# IO.net
KiCad netlist of a schematic drawn in Altium Designer
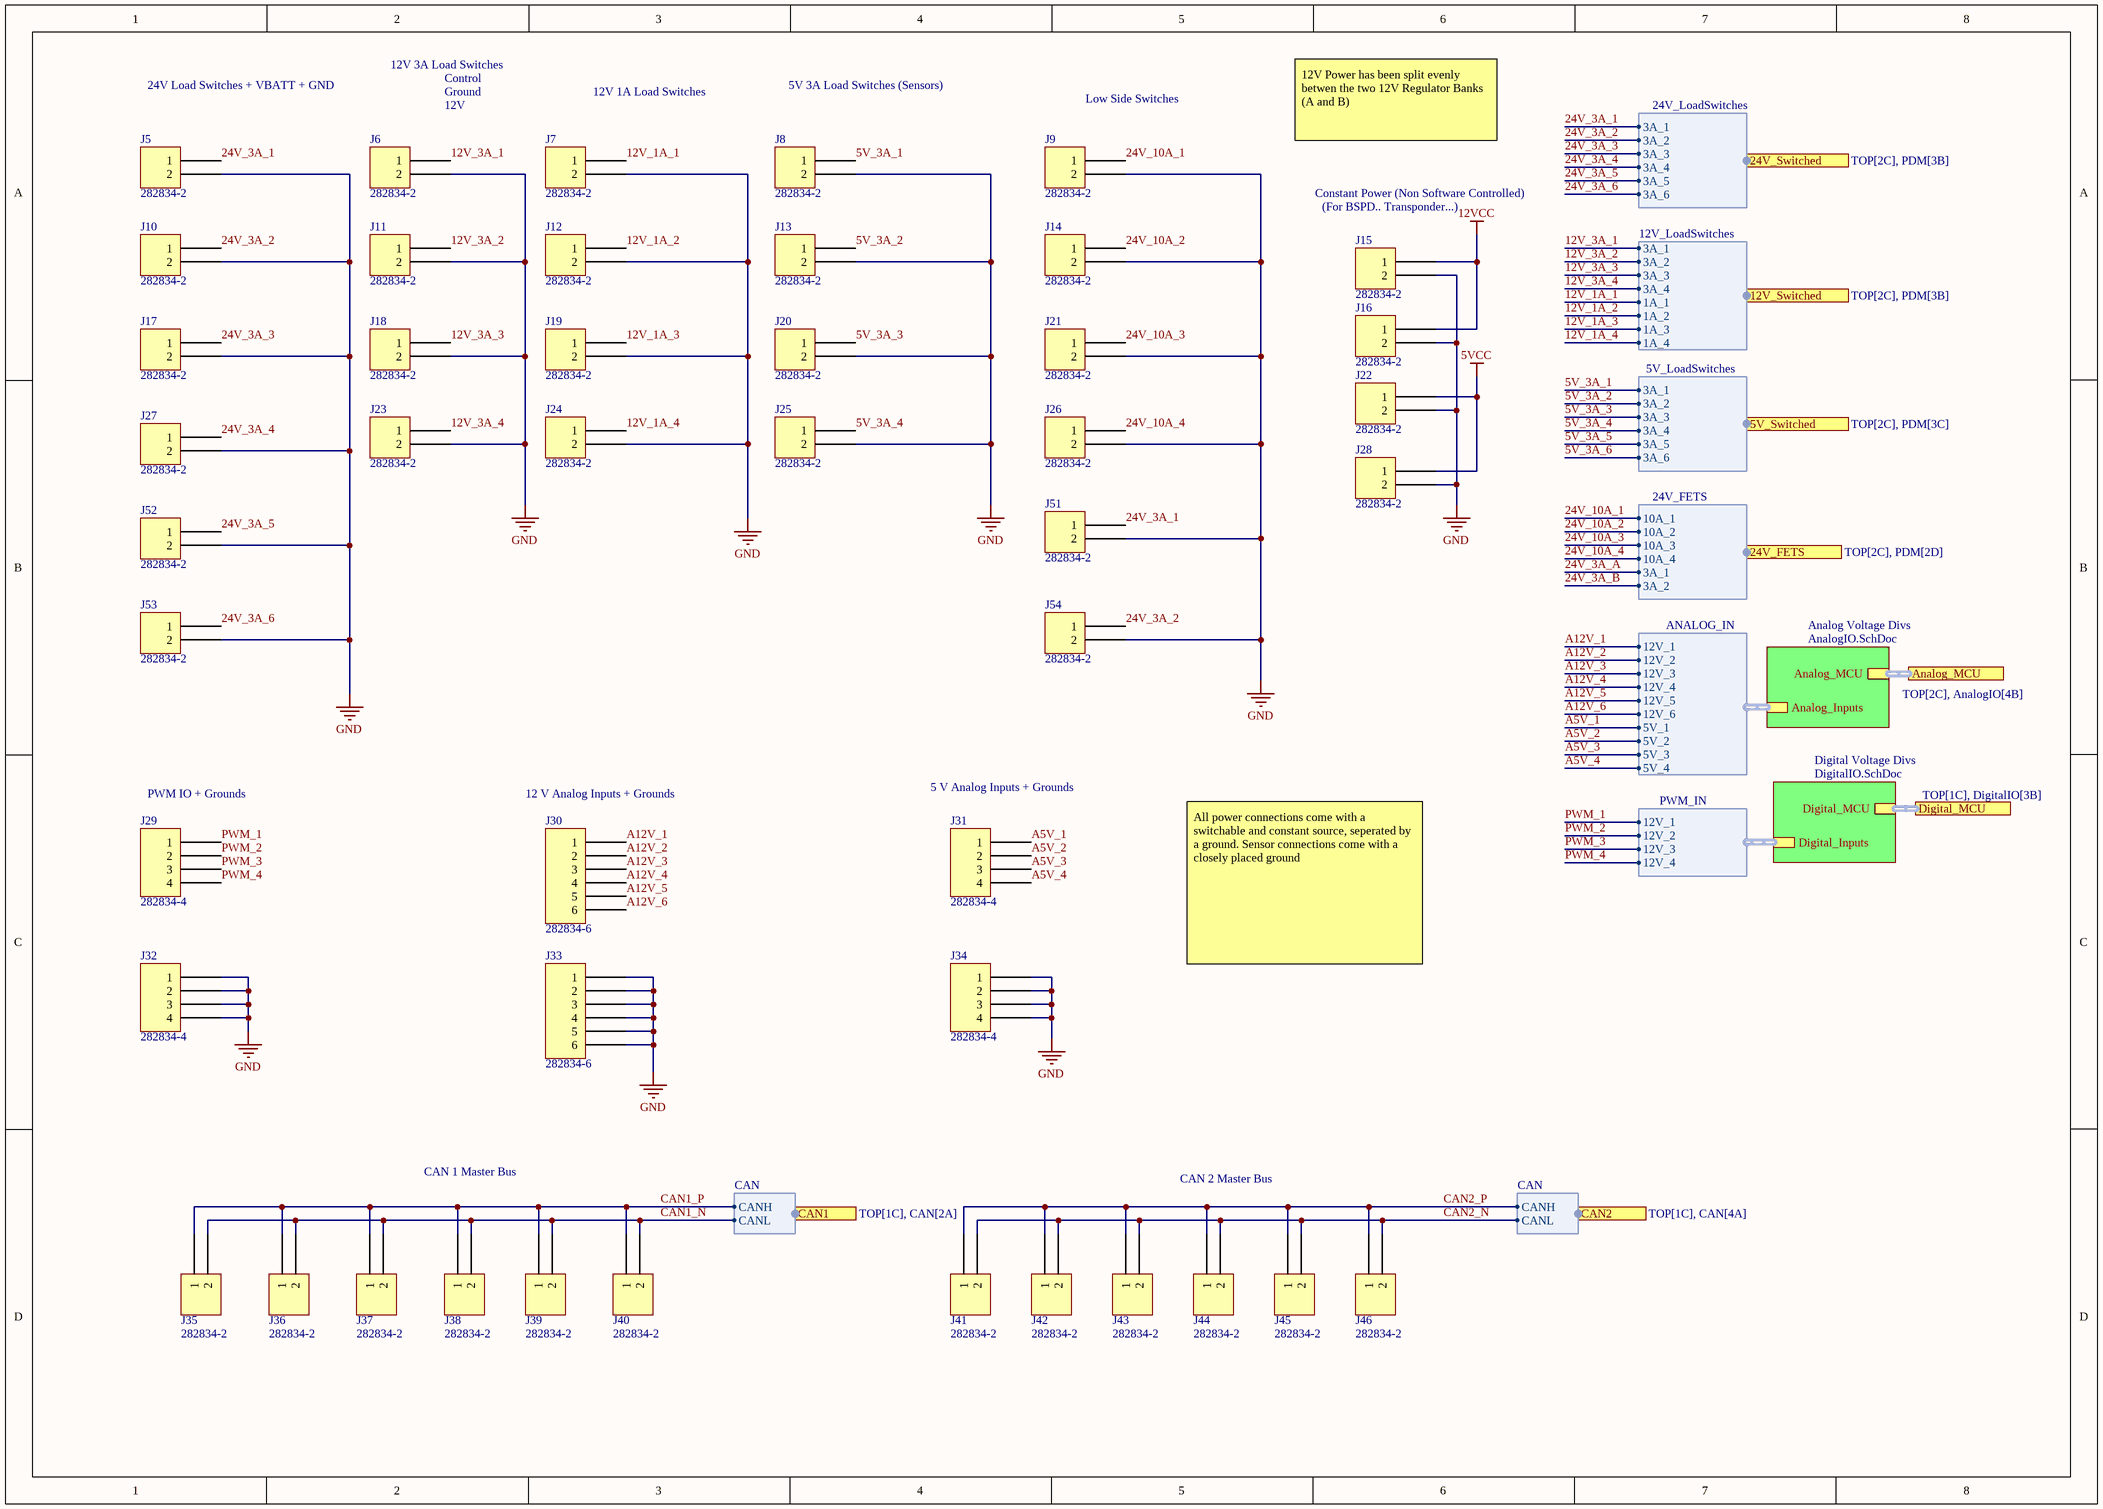
[diagram p0: IO.SchDoc]

(export (version "E")
  (design (tool "Eeschema 10.0.6"))
  (components
    (comp (ref "J5")
      (value "282834-2")
      (footprint "TE 282834-2")
      (description "TERM BLK 2P SIDE ENT 2.54MM PCB")
      (libsource (lib "") (part "2 Pin_1"))
    )
    (comp (ref "J6")
      (value "282834-2")
      (footprint "TE 282834-2")
      (description "TERM BLK 2P SIDE ENT 2.54MM PCB")
      (libsource (lib "") (part "2 Pin_1"))
    )
    (comp (ref "J7")
      (value "282834-2")
      (footprint "TE 282834-2")
      (description "TERM BLK 2P SIDE ENT 2.54MM PCB")
      (libsource (lib "") (part "2 Pin_1"))
    )
    (comp (ref "J8")
      (value "282834-2")
      (footprint "TE 282834-2")
      (description "TERM BLK 2P SIDE ENT 2.54MM PCB")
      (libsource (lib "") (part "2 Pin_1"))
    )
    (comp (ref "J9")
      (value "282834-2")
      (footprint "TE 282834-2")
      (description "TERM BLK 2P SIDE ENT 2.54MM PCB")
      (libsource (lib "") (part "2 Pin_1"))
    )
    (comp (ref "J10")
      (value "282834-2")
      (footprint "TE 282834-2")
      (description "TERM BLK 2P SIDE ENT 2.54MM PCB")
      (libsource (lib "") (part "2 Pin_1"))
    )
    (comp (ref "J11")
      (value "282834-2")
      (footprint "TE 282834-2")
      (description "TERM BLK 2P SIDE ENT 2.54MM PCB")
      (libsource (lib "") (part "2 Pin_1"))
    )
    (comp (ref "J12")
      (value "282834-2")
      (footprint "TE 282834-2")
      (description "TERM BLK 2P SIDE ENT 2.54MM PCB")
      (libsource (lib "") (part "2 Pin_1"))
    )
    (comp (ref "J13")
      (value "282834-2")
      (footprint "TE 282834-2")
      (description "TERM BLK 2P SIDE ENT 2.54MM PCB")
      (libsource (lib "") (part "2 Pin_1"))
    )
    (comp (ref "J14")
      (value "282834-2")
      (footprint "TE 282834-2")
      (description "TERM BLK 2P SIDE ENT 2.54MM PCB")
      (libsource (lib "") (part "2 Pin_1"))
    )
    (comp (ref "J15")
      (value "282834-2")
      (footprint "TE 282834-2")
      (description "TERM BLK 2P SIDE ENT 2.54MM PCB")
      (libsource (lib "") (part "2 Pin_1"))
    )
    (comp (ref "J16")
      (value "282834-2")
      (footprint "TE 282834-2")
      (description "TERM BLK 2P SIDE ENT 2.54MM PCB")
      (libsource (lib "") (part "2 Pin_1"))
    )
    (comp (ref "J17")
      (value "282834-2")
      (footprint "TE 282834-2")
      (description "TERM BLK 2P SIDE ENT 2.54MM PCB")
      (libsource (lib "") (part "2 Pin_1"))
    )
    (comp (ref "J18")
      (value "282834-2")
      (footprint "TE 282834-2")
      (description "TERM BLK 2P SIDE ENT 2.54MM PCB")
      (libsource (lib "") (part "2 Pin_1"))
    )
    (comp (ref "J19")
      (value "282834-2")
      (footprint "TE 282834-2")
      (description "TERM BLK 2P SIDE ENT 2.54MM PCB")
      (libsource (lib "") (part "2 Pin_1"))
    )
    (comp (ref "J20")
      (value "282834-2")
      (footprint "TE 282834-2")
      (description "TERM BLK 2P SIDE ENT 2.54MM PCB")
      (libsource (lib "") (part "2 Pin_1"))
    )
    (comp (ref "J21")
      (value "282834-2")
      (footprint "TE 282834-2")
      (description "TERM BLK 2P SIDE ENT 2.54MM PCB")
      (libsource (lib "") (part "2 Pin_1"))
    )
    (comp (ref "J22")
      (value "282834-2")
      (footprint "TE 282834-2")
      (description "TERM BLK 2P SIDE ENT 2.54MM PCB")
      (libsource (lib "") (part "2 Pin_1"))
    )
    (comp (ref "J23")
      (value "282834-2")
      (footprint "TE 282834-2")
      (description "TERM BLK 2P SIDE ENT 2.54MM PCB")
      (libsource (lib "") (part "2 Pin_1"))
    )
    (comp (ref "J24")
      (value "282834-2")
      (footprint "TE 282834-2")
      (description "TERM BLK 2P SIDE ENT 2.54MM PCB")
      (libsource (lib "") (part "2 Pin_1"))
    )
    (comp (ref "J25")
      (value "282834-2")
      (footprint "TE 282834-2")
      (description "TERM BLK 2P SIDE ENT 2.54MM PCB")
      (libsource (lib "") (part "2 Pin_1"))
    )
    (comp (ref "J26")
      (value "282834-2")
      (footprint "TE 282834-2")
      (description "TERM BLK 2P SIDE ENT 2.54MM PCB")
      (libsource (lib "") (part "2 Pin_1"))
    )
    (comp (ref "J27")
      (value "282834-2")
      (footprint "TE 282834-2")
      (description "TERM BLK 2P SIDE ENT 2.54MM PCB")
      (libsource (lib "") (part "2 Pin_1"))
    )
    (comp (ref "J28")
      (value "282834-2")
      (footprint "TE 282834-2")
      (description "TERM BLK 2P SIDE ENT 2.54MM PCB")
      (libsource (lib "") (part "2 Pin_1"))
    )
    (comp (ref "J29")
      (value "282834-4")
      (footprint "TE 282834-4")
      (description "TERM BLK 4P SIDE ENT 2.54MM PCB")
      (libsource (lib "altium_library") (part "4 Pin"))
    )
    (comp (ref "J30")
      (value "282834-6")
      (footprint "TE 282834-6")
      (description "TERM BLK 6P SIDE ENT 2.54MM PCB")
      (libsource (lib "altium_library") (part "6 Pin"))
    )
    (comp (ref "J31")
      (value "282834-4")
      (footprint "TE 282834-4")
      (description "TERM BLK 4P SIDE ENT 2.54MM PCB")
      (libsource (lib "altium_library") (part "4 Pin"))
    )
    (comp (ref "J32")
      (value "282834-4")
      (footprint "TE 282834-4")
      (description "TERM BLK 4P SIDE ENT 2.54MM PCB")
      (libsource (lib "altium_library") (part "4 Pin"))
    )
    (comp (ref "J33")
      (value "282834-6")
      (footprint "TE 282834-6")
      (description "TERM BLK 6P SIDE ENT 2.54MM PCB")
      (libsource (lib "altium_library") (part "6 Pin"))
    )
    (comp (ref "J34")
      (value "282834-4")
      (footprint "TE 282834-4")
      (description "TERM BLK 4P SIDE ENT 2.54MM PCB")
      (libsource (lib "altium_library") (part "4 Pin"))
    )
    (comp (ref "J35")
      (value "282834-2")
      (footprint "TE 282834-2")
      (description "TERM BLK 2P SIDE ENT 2.54MM PCB")
      (libsource (lib "altium_library") (part "2 Pin"))
    )
    (comp (ref "J36")
      (value "282834-2")
      (footprint "TE 282834-2")
      (description "TERM BLK 2P SIDE ENT 2.54MM PCB")
      (libsource (lib "altium_library") (part "2 Pin"))
    )
    (comp (ref "J37")
      (value "282834-2")
      (footprint "TE 282834-2")
      (description "TERM BLK 2P SIDE ENT 2.54MM PCB")
      (libsource (lib "altium_library") (part "2 Pin"))
    )
    (comp (ref "J38")
      (value "282834-2")
      (footprint "TE 282834-2")
      (description "TERM BLK 2P SIDE ENT 2.54MM PCB")
      (libsource (lib "altium_library") (part "2 Pin"))
    )
    (comp (ref "J39")
      (value "282834-2")
      (footprint "TE 282834-2")
      (description "TERM BLK 2P SIDE ENT 2.54MM PCB")
      (libsource (lib "altium_library") (part "2 Pin"))
    )
    (comp (ref "J40")
      (value "282834-2")
      (footprint "TE 282834-2")
      (description "TERM BLK 2P SIDE ENT 2.54MM PCB")
      (libsource (lib "altium_library") (part "2 Pin"))
    )
    (comp (ref "J41")
      (value "282834-2")
      (footprint "TE 282834-2")
      (description "TERM BLK 2P SIDE ENT 2.54MM PCB")
      (libsource (lib "altium_library") (part "2 Pin"))
    )
    (comp (ref "J42")
      (value "282834-2")
      (footprint "TE 282834-2")
      (description "TERM BLK 2P SIDE ENT 2.54MM PCB")
      (libsource (lib "altium_library") (part "2 Pin"))
    )
    (comp (ref "J43")
      (value "282834-2")
      (footprint "TE 282834-2")
      (description "TERM BLK 2P SIDE ENT 2.54MM PCB")
      (libsource (lib "altium_library") (part "2 Pin"))
    )
    (comp (ref "J44")
      (value "282834-2")
      (footprint "TE 282834-2")
      (description "TERM BLK 2P SIDE ENT 2.54MM PCB")
      (libsource (lib "altium_library") (part "2 Pin"))
    )
    (comp (ref "J45")
      (value "282834-2")
      (footprint "TE 282834-2")
      (description "TERM BLK 2P SIDE ENT 2.54MM PCB")
      (libsource (lib "altium_library") (part "2 Pin"))
    )
    (comp (ref "J46")
      (value "282834-2")
      (footprint "TE 282834-2")
      (description "TERM BLK 2P SIDE ENT 2.54MM PCB")
      (libsource (lib "altium_library") (part "2 Pin"))
    )
    (comp (ref "J51")
      (value "282834-2")
      (footprint "TE 282834-2")
      (description "TERM BLK 2P SIDE ENT 2.54MM PCB")
      (libsource (lib "") (part "2 Pin_1"))
    )
    (comp (ref "J52")
      (value "282834-2")
      (footprint "TE 282834-2")
      (description "TERM BLK 2P SIDE ENT 2.54MM PCB")
      (libsource (lib "") (part "2 Pin_1"))
    )
    (comp (ref "J53")
      (value "282834-2")
      (footprint "TE 282834-2")
      (description "TERM BLK 2P SIDE ENT 2.54MM PCB")
      (libsource (lib "") (part "2 Pin_1"))
    )
    (comp (ref "J54")
      (value "282834-2")
      (footprint "TE 282834-2")
      (description "TERM BLK 2P SIDE ENT 2.54MM PCB")
      (libsource (lib "") (part "2 Pin_1"))
    )
  )
  (nets
    (net (code "10") (name "/5V_3A_1") (class "Default")
      (node (ref "J8") (pin "1") (pinfunction "1_1") (pintype "passive"))
    )
    (net (code "11") (name "/5V_3A_2") (class "Default")
      (node (ref "J13") (pin "1") (pinfunction "1_1") (pintype "passive"))
    )
    (net (code "12") (name "/5V_3A_3") (class "Default")
      (node (ref "J20") (pin "1") (pinfunction "1_1") (pintype "passive"))
    )
    (net (code "13") (name "/5V_3A_4") (class "Default")
      (node (ref "J25") (pin "1") (pinfunction "1_1") (pintype "passive"))
    )
    (net (code "16") (name "/12V_1A_1") (class "Default")
      (node (ref "J7") (pin "1") (pinfunction "1_1") (pintype "passive"))
    )
    (net (code "17") (name "/12V_1A_2") (class "Default")
      (node (ref "J12") (pin "1") (pinfunction "1_1") (pintype "passive"))
    )
    (net (code "18") (name "/12V_1A_3") (class "Default")
      (node (ref "J19") (pin "1") (pinfunction "1_1") (pintype "passive"))
    )
    (net (code "19") (name "/12V_1A_4") (class "Default")
      (node (ref "J24") (pin "1") (pinfunction "1_1") (pintype "passive"))
    )
    (net (code "20") (name "/12V_3A_1") (class "Default")
      (node (ref "J6") (pin "1") (pinfunction "1_1") (pintype "passive"))
    )
    (net (code "21") (name "/12V_3A_2") (class "Default")
      (node (ref "J11") (pin "1") (pinfunction "1_1") (pintype "passive"))
    )
    (net (code "22") (name "/12V_3A_3") (class "Default")
      (node (ref "J18") (pin "1") (pinfunction "1_1") (pintype "passive"))
    )
    (net (code "23") (name "/12V_3A_4") (class "Default")
      (node (ref "J23") (pin "1") (pinfunction "1_1") (pintype "passive"))
    )
    (net (code "24") (name "/24V_3A_1") (class "Default")
      (node (ref "J5") (pin "1") (pinfunction "1_1") (pintype "passive"))
      (node (ref "J51") (pin "1") (pinfunction "1_1") (pintype "passive"))
    )
    (net (code "25") (name "/24V_3A_2") (class "Default")
      (node (ref "J10") (pin "1") (pinfunction "1_1") (pintype "passive"))
      (node (ref "J54") (pin "1") (pinfunction "1_1") (pintype "passive"))
    )
    (net (code "26") (name "/24V_3A_3") (class "Default")
      (node (ref "J17") (pin "1") (pinfunction "1_1") (pintype "passive"))
    )
    (net (code "27") (name "/24V_3A_4") (class "Default")
      (node (ref "J27") (pin "1") (pinfunction "1_1") (pintype "passive"))
    )
    (net (code "28") (name "/24V_3A_5") (class "Default")
      (node (ref "J52") (pin "1") (pinfunction "1_1") (pintype "passive"))
    )
    (net (code "29") (name "/24V_3A_6") (class "Default")
      (node (ref "J53") (pin "1") (pinfunction "1_1") (pintype "passive"))
    )
    (net (code "32") (name "/24V_10A_1") (class "Default")
      (node (ref "J9") (pin "1") (pinfunction "1_1") (pintype "passive"))
    )
    (net (code "33") (name "/24V_10A_2") (class "Default")
      (node (ref "J14") (pin "1") (pinfunction "1_1") (pintype "passive"))
    )
    (net (code "34") (name "/24V_10A_3") (class "Default")
      (node (ref "J21") (pin "1") (pinfunction "1_1") (pintype "passive"))
    )
    (net (code "35") (name "/24V_10A_4") (class "Default")
      (node (ref "J26") (pin "1") (pinfunction "1_1") (pintype "passive"))
    )
    (net (code "36") (name "/A5V_1") (class "Default")
      (node (ref "J31") (pin "1") (pinfunction "1_1") (pintype "passive"))
    )
    (net (code "37") (name "/A5V_2") (class "Default")
      (node (ref "J31") (pin "2") (pinfunction "2_2") (pintype "passive"))
    )
    (net (code "38") (name "/A5V_3") (class "Default")
      (node (ref "J31") (pin "3") (pinfunction "3_3") (pintype "passive"))
    )
    (net (code "39") (name "/A5V_4") (class "Default")
      (node (ref "J31") (pin "4") (pinfunction "4_4") (pintype "passive"))
    )
    (net (code "40") (name "/A12V_1") (class "Default")
      (node (ref "J30") (pin "1") (pinfunction "1_1") (pintype "passive"))
    )
    (net (code "41") (name "/A12V_2") (class "Default")
      (node (ref "J30") (pin "2") (pinfunction "2_2") (pintype "passive"))
    )
    (net (code "42") (name "/A12V_3") (class "Default")
      (node (ref "J30") (pin "3") (pinfunction "3_3") (pintype "passive"))
    )
    (net (code "43") (name "/A12V_4") (class "Default")
      (node (ref "J30") (pin "4") (pinfunction "4_4") (pintype "passive"))
    )
    (net (code "44") (name "/A12V_5") (class "Default")
      (node (ref "J30") (pin "5") (pinfunction "5_5") (pintype "passive"))
    )
    (net (code "45") (name "/A12V_6") (class "Default")
      (node (ref "J30") (pin "6") (pinfunction "6_6") (pintype "passive"))
    )
    (net (code "47") (name "/CAN1_N") (class "Default")
      (node (ref "J35") (pin "2") (pinfunction "2_2") (pintype "passive"))
      (node (ref "J36") (pin "2") (pinfunction "2_2") (pintype "passive"))
      (node (ref "J37") (pin "2") (pinfunction "2_2") (pintype "passive"))
      (node (ref "J38") (pin "2") (pinfunction "2_2") (pintype "passive"))
      (node (ref "J39") (pin "2") (pinfunction "2_2") (pintype "passive"))
      (node (ref "J40") (pin "2") (pinfunction "2_2") (pintype "passive"))
    )
    (net (code "48") (name "/CAN1_P") (class "Default")
      (node (ref "J35") (pin "1") (pinfunction "1_1") (pintype "passive"))
      (node (ref "J36") (pin "1") (pinfunction "1_1") (pintype "passive"))
      (node (ref "J37") (pin "1") (pinfunction "1_1") (pintype "passive"))
      (node (ref "J38") (pin "1") (pinfunction "1_1") (pintype "passive"))
      (node (ref "J39") (pin "1") (pinfunction "1_1") (pintype "passive"))
      (node (ref "J40") (pin "1") (pinfunction "1_1") (pintype "passive"))
    )
    (net (code "49") (name "/CAN2_N") (class "Default")
      (node (ref "J41") (pin "2") (pinfunction "2_2") (pintype "passive"))
      (node (ref "J42") (pin "2") (pinfunction "2_2") (pintype "passive"))
      (node (ref "J43") (pin "2") (pinfunction "2_2") (pintype "passive"))
      (node (ref "J44") (pin "2") (pinfunction "2_2") (pintype "passive"))
      (node (ref "J45") (pin "2") (pinfunction "2_2") (pintype "passive"))
      (node (ref "J46") (pin "2") (pinfunction "2_2") (pintype "passive"))
    )
    (net (code "50") (name "/CAN2_P") (class "Default")
      (node (ref "J41") (pin "1") (pinfunction "1_1") (pintype "passive"))
      (node (ref "J42") (pin "1") (pinfunction "1_1") (pintype "passive"))
      (node (ref "J43") (pin "1") (pinfunction "1_1") (pintype "passive"))
      (node (ref "J44") (pin "1") (pinfunction "1_1") (pintype "passive"))
      (node (ref "J45") (pin "1") (pinfunction "1_1") (pintype "passive"))
      (node (ref "J46") (pin "1") (pinfunction "1_1") (pintype "passive"))
    )
    (net (code "52") (name "/PWM_1") (class "Default")
      (node (ref "J29") (pin "1") (pinfunction "1_1") (pintype "passive"))
    )
    (net (code "53") (name "/PWM_2") (class "Default")
      (node (ref "J29") (pin "2") (pinfunction "2_2") (pintype "passive"))
    )
    (net (code "54") (name "/PWM_3") (class "Default")
      (node (ref "J29") (pin "3") (pinfunction "3_3") (pintype "passive"))
    )
    (net (code "55") (name "/PWM_4") (class "Default")
      (node (ref "J29") (pin "4") (pinfunction "4_4") (pintype "passive"))
    )
    (net (code "63") (name "5VCC") (class "Default")
      (node (ref "J22") (pin "1") (pinfunction "1_1") (pintype "passive"))
      (node (ref "J28") (pin "1") (pinfunction "1_1") (pintype "passive"))
    )
    (net (code "64") (name "12VCC") (class "Default")
      (node (ref "J15") (pin "1") (pinfunction "1_1") (pintype "passive"))
      (node (ref "J16") (pin "1") (pinfunction "1_1") (pintype "passive"))
    )
    (net (code "65") (name "GND") (class "Default")
      (node (ref "J10") (pin "2") (pinfunction "2_2") (pintype "passive"))
      (node (ref "J11") (pin "2") (pinfunction "2_2") (pintype "passive"))
      (node (ref "J12") (pin "2") (pinfunction "2_2") (pintype "passive"))
      (node (ref "J13") (pin "2") (pinfunction "2_2") (pintype "passive"))
      (node (ref "J14") (pin "2") (pinfunction "2_2") (pintype "passive"))
      (node (ref "J15") (pin "2") (pinfunction "2_2") (pintype "passive"))
      (node (ref "J16") (pin "2") (pinfunction "2_2") (pintype "passive"))
      (node (ref "J17") (pin "2") (pinfunction "2_2") (pintype "passive"))
      (node (ref "J18") (pin "2") (pinfunction "2_2") (pintype "passive"))
      (node (ref "J19") (pin "2") (pinfunction "2_2") (pintype "passive"))
      (node (ref "J20") (pin "2") (pinfunction "2_2") (pintype "passive"))
      (node (ref "J21") (pin "2") (pinfunction "2_2") (pintype "passive"))
      (node (ref "J22") (pin "2") (pinfunction "2_2") (pintype "passive"))
      (node (ref "J23") (pin "2") (pinfunction "2_2") (pintype "passive"))
      (node (ref "J24") (pin "2") (pinfunction "2_2") (pintype "passive"))
      (node (ref "J25") (pin "2") (pinfunction "2_2") (pintype "passive"))
      (node (ref "J26") (pin "2") (pinfunction "2_2") (pintype "passive"))
      (node (ref "J27") (pin "2") (pinfunction "2_2") (pintype "passive"))
      (node (ref "J28") (pin "2") (pinfunction "2_2") (pintype "passive"))
      (node (ref "J32") (pin "1") (pinfunction "1_1") (pintype "passive"))
      (node (ref "J32") (pin "2") (pinfunction "2_2") (pintype "passive"))
      (node (ref "J32") (pin "3") (pinfunction "3_3") (pintype "passive"))
      (node (ref "J32") (pin "4") (pinfunction "4_4") (pintype "passive"))
      (node (ref "J33") (pin "1") (pinfunction "1_1") (pintype "passive"))
      (node (ref "J33") (pin "2") (pinfunction "2_2") (pintype "passive"))
      (node (ref "J33") (pin "3") (pinfunction "3_3") (pintype "passive"))
      (node (ref "J33") (pin "4") (pinfunction "4_4") (pintype "passive"))
      (node (ref "J33") (pin "5") (pinfunction "5_5") (pintype "passive"))
      (node (ref "J33") (pin "6") (pinfunction "6_6") (pintype "passive"))
      (node (ref "J34") (pin "1") (pinfunction "1_1") (pintype "passive"))
      (node (ref "J34") (pin "2") (pinfunction "2_2") (pintype "passive"))
      (node (ref "J34") (pin "3") (pinfunction "3_3") (pintype "passive"))
      (node (ref "J34") (pin "4") (pinfunction "4_4") (pintype "passive"))
      (node (ref "J5") (pin "2") (pinfunction "2_2") (pintype "passive"))
      (node (ref "J51") (pin "2") (pinfunction "2_2") (pintype "passive"))
      (node (ref "J52") (pin "2") (pinfunction "2_2") (pintype "passive"))
      (node (ref "J53") (pin "2") (pinfunction "2_2") (pintype "passive"))
      (node (ref "J54") (pin "2") (pinfunction "2_2") (pintype "passive"))
      (node (ref "J6") (pin "2") (pinfunction "2_2") (pintype "passive"))
      (node (ref "J7") (pin "2") (pinfunction "2_2") (pintype "passive"))
      (node (ref "J8") (pin "2") (pinfunction "2_2") (pintype "passive"))
      (node (ref "J9") (pin "2") (pinfunction "2_2") (pintype "passive"))
    )
  )
)
